# P1SwitchDemo.net
KiCad netlist of a schematic drawn in EAGLE
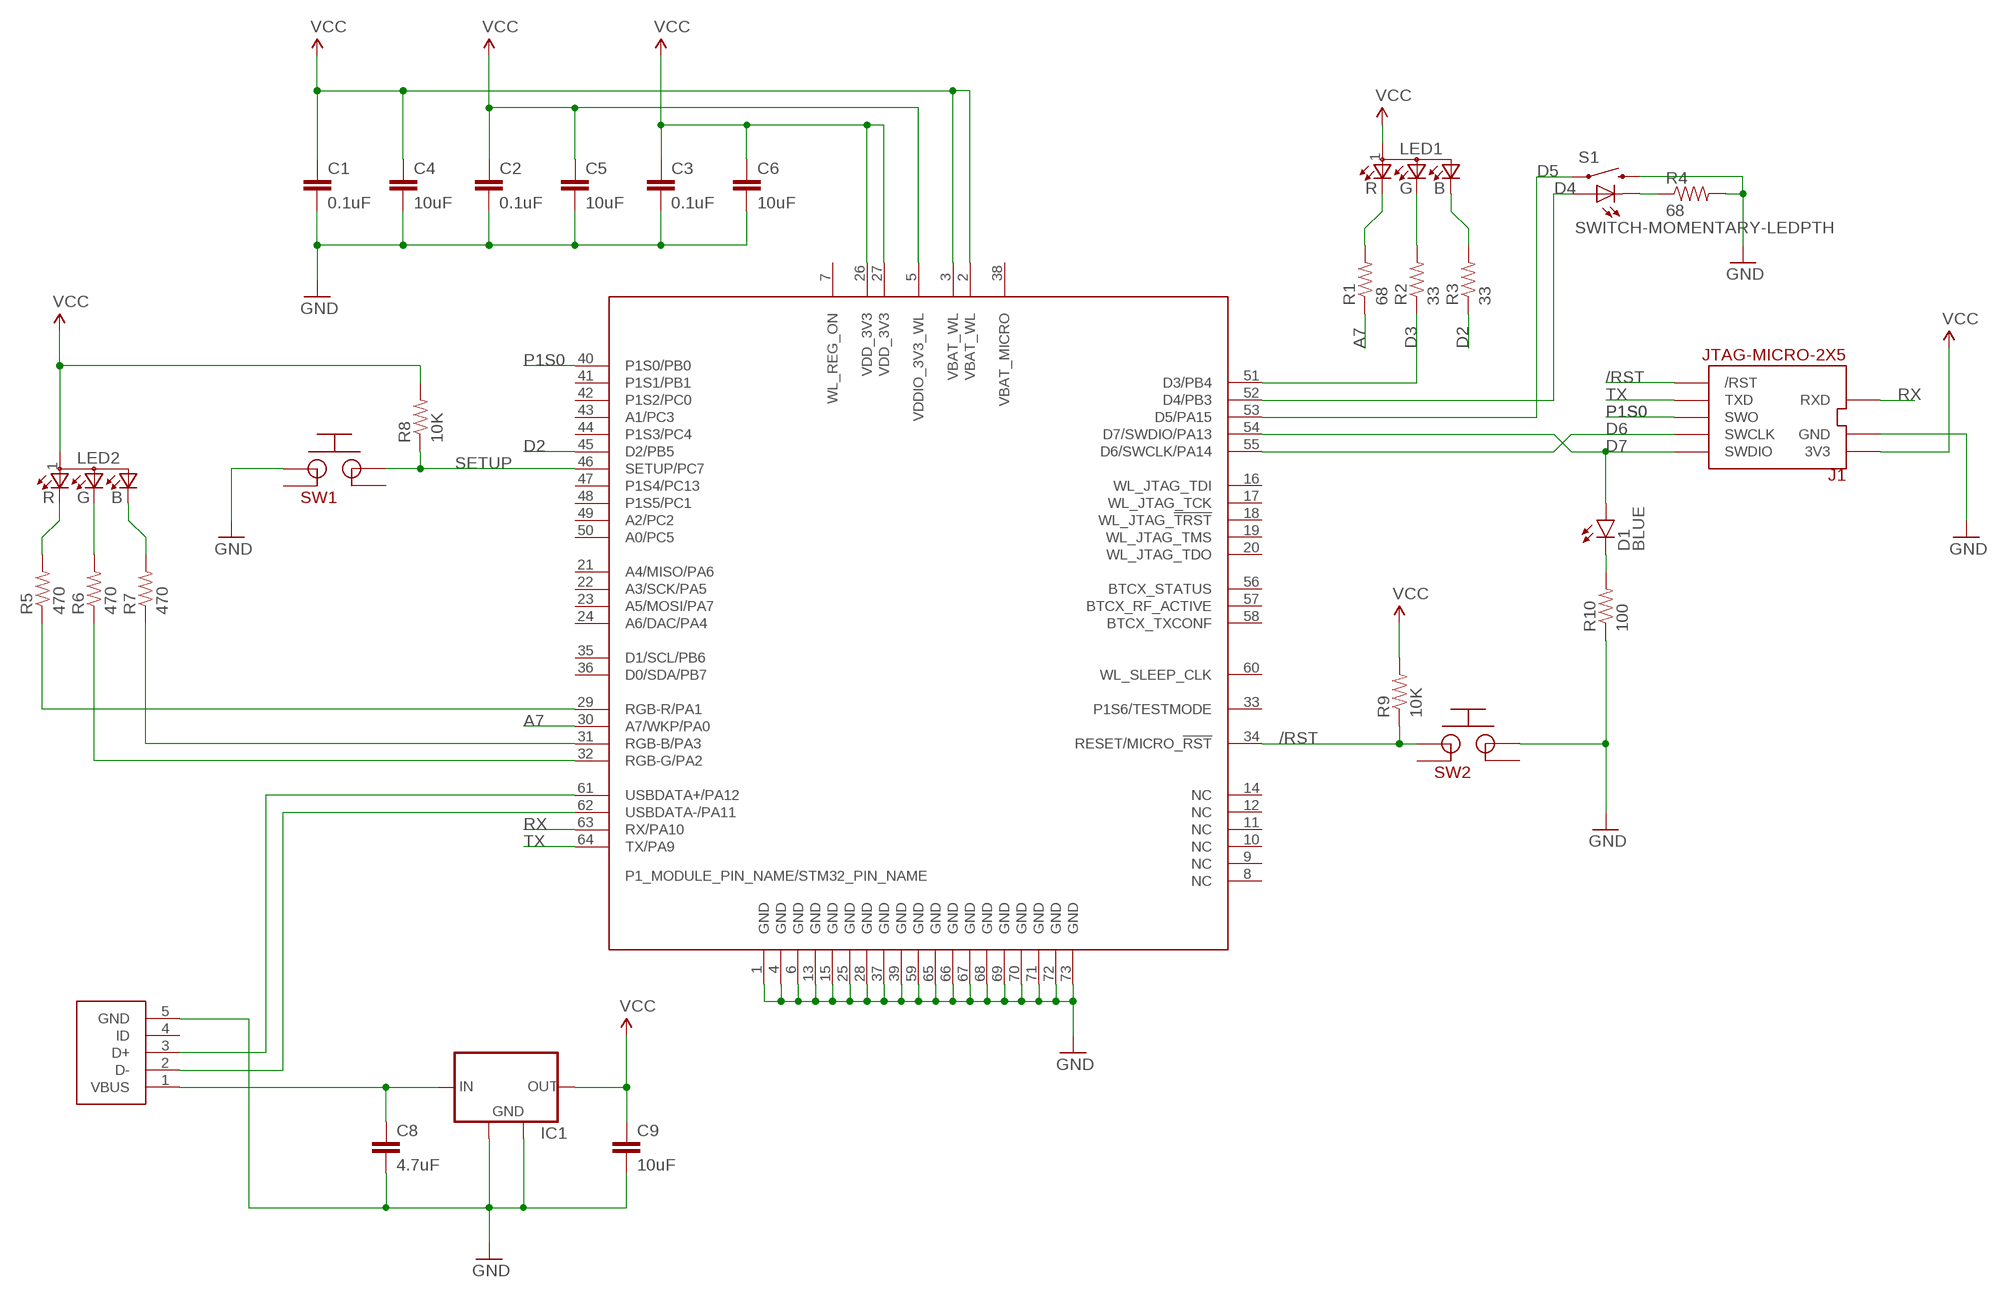
[diagram p0: schematic, sheet 1]

(export (version "E")
  (design (tool "Eeschema 10.0.6"))
  (components
    (comp (ref "C1")
      (value "0.1uF")
      (footprint "eagle-import:0603-CAP")
      (libsource (lib "eagle-import") (part "CAP-0.1UF-0603"))
    )
    (comp (ref "C2")
      (value "0.1uF")
      (footprint "eagle-import:0603-CAP")
      (libsource (lib "eagle-import") (part "CAP-0.1UF-0603"))
    )
    (comp (ref "C3")
      (value "0.1uF")
      (footprint "eagle-import:0603-CAP")
      (libsource (lib "eagle-import") (part "CAP-0.1UF-0603"))
    )
    (comp (ref "C4")
      (value "10uF")
      (footprint "eagle-import:0603-CAP")
      (libsource (lib "eagle-import") (part "CAP-10UF-0603"))
    )
    (comp (ref "C5")
      (value "10uF")
      (footprint "eagle-import:0603-CAP")
      (libsource (lib "eagle-import") (part "CAP-10UF-0603"))
    )
    (comp (ref "C6")
      (value "10uF")
      (footprint "eagle-import:0603-CAP")
      (libsource (lib "eagle-import") (part "CAP-10UF-0603"))
    )
    (comp (ref "C8")
      (value "4.7uF")
      (footprint "eagle-import:0603-CAP")
      (libsource (lib "eagle-import") (part "CAP-4.7UF-0603"))
    )
    (comp (ref "C9")
      (value "10uF")
      (footprint "eagle-import:0603-CAP")
      (libsource (lib "eagle-import") (part "CAP-10UF-0603"))
    )
    (comp (ref "D1")
      (value "BLUE")
      (footprint "eagle-import:LED-0603")
      (libsource (lib "eagle-import") (part "LED-BLUE0603"))
    )
    (comp (ref "IC1")
      (value "MCP1825S-SOT223")
      (footprint "eagle-import:SOT223")
      (libsource (lib "eagle-import") (part "MCP1825S-SOT223"))
    )
    (comp (ref "J1")
      (value "JTAG-MICRO-2X5")
      (footprint "eagle-import:JTAG-MICRO-2X5")
      (libsource (lib "eagle-import") (part "JTAG-MICRO-2X5"))
    )
    (comp (ref "LED1")
      (value "LED-RGB-CREE-SMD")
      (footprint "eagle-import:LED-RGB-CREE-SMD")
      (libsource (lib "eagle-import") (part "LED-RGB-CREE-SMD"))
    )
    (comp (ref "LED2")
      (value "LED-RGB-CREE-SMD")
      (footprint "eagle-import:LED-RGB-CREE-SMD")
      (libsource (lib "eagle-import") (part "LED-RGB-CREE-SMD"))
    )
    (comp (ref "R1")
      (value "68")
      (footprint "eagle-import:0603-RES")
      (libsource (lib "eagle-import") (part "RES-68-0603.DEV"))
    )
    (comp (ref "R2")
      (value "33")
      (footprint "eagle-import:0603-RES")
      (libsource (lib "eagle-import") (part "RES-33-0603.DEV"))
    )
    (comp (ref "R3")
      (value "33")
      (footprint "eagle-import:0603-RES")
      (libsource (lib "eagle-import") (part "RES-33-0603.DEV"))
    )
    (comp (ref "R4")
      (value "68")
      (footprint "eagle-import:0603-RES")
      (libsource (lib "eagle-import") (part "RES-68-0603.DEV"))
    )
    (comp (ref "R5")
      (value "470")
      (footprint "eagle-import:0603-RES")
      (libsource (lib "eagle-import") (part "RES-470-0603"))
    )
    (comp (ref "R6")
      (value "470")
      (footprint "eagle-import:0603-RES")
      (libsource (lib "eagle-import") (part "RES-470-0603"))
    )
    (comp (ref "R7")
      (value "470")
      (footprint "eagle-import:0603-RES")
      (libsource (lib "eagle-import") (part "RES-470-0603"))
    )
    (comp (ref "R8")
      (value "10K")
      (footprint "eagle-import:0603-RES")
      (libsource (lib "eagle-import") (part "RES-10K-06030603"))
    )
    (comp (ref "R9")
      (value "10K")
      (footprint "eagle-import:0603-RES")
      (libsource (lib "eagle-import") (part "RES-10K-06030603"))
    )
    (comp (ref "R10")
      (value "100")
      (footprint "eagle-import:0603-RES")
      (libsource (lib "eagle-import") (part "RES-100-0603.DEV"))
    )
    (comp (ref "S1")
      (value "SWITCH-MOMENTARY-LEDPTH")
      (footprint "eagle-import:TACTILE-PTH-LED-12MM")
      (libsource (lib "eagle-import") (part "SWITCH-MOMENTARY-LEDPTH"))
    )
    (comp (ref "SW1")
      (value "SWITCH-PTS645")
      (footprint "eagle-import:SWITCH-PTS645")
      (libsource (lib "eagle-import") (part "SWITCH-PTS645"))
    )
    (comp (ref "SW2")
      (value "SWITCH-PTS645")
      (footprint "eagle-import:SWITCH-PTS645")
      (libsource (lib "eagle-import") (part "SWITCH-PTS645"))
    )
    (comp (ref "U$4")
      (value "USB-MICRO-B-SOCKET-AMPHENOL")
      (footprint "eagle-import:USB-B-SMT-AMPHENOL")
      (libsource (lib "eagle-import") (part "USB-MICRO-B-SOCKET-AMPHENOL"))
    )
    (comp (ref "U$6")
      (value "P1")
      (footprint "eagle-import:WM-N-BM-14")
      (libsource (lib "eagle-import") (part "P1"))
    )
  )
  (nets
    (net (code "1") (name "/A7") (class "Default")
      (node (ref "R1") (pin "1") (pinfunction "1_1") (pintype "passive"))
      (node (ref "U$6") (pin "30") (pinfunction "A7/WKP/PA0_30") (pintype "bidirectional"))
    )
    (net (code "2") (name "/D2") (class "Default")
      (node (ref "R3") (pin "1") (pinfunction "1_1") (pintype "passive"))
      (node (ref "U$6") (pin "45") (pinfunction "D2/PB5_45") (pintype "bidirectional"))
    )
    (net (code "3") (name "/D3") (class "Default")
      (node (ref "R2") (pin "1") (pinfunction "1_1") (pintype "passive"))
      (node (ref "U$6") (pin "51") (pinfunction "D3/PB4_51") (pintype "bidirectional"))
    )
    (net (code "4") (name "/D4") (class "Default")
      (node (ref "S1") (pin "A") (pinfunction "A_A") (pintype "passive"))
      (node (ref "U$6") (pin "52") (pinfunction "D4/PB3_52") (pintype "bidirectional"))
    )
    (net (code "5") (name "/D5") (class "Default")
      (node (ref "S1") (pin "4") (pinfunction "1_4") (pintype "passive"))
      (node (ref "U$6") (pin "53") (pinfunction "D5/PA15_53") (pintype "bidirectional"))
    )
    (net (code "6") (name "/D6") (class "Default")
      (node (ref "J1") (pin "4") (pinfunction "SWCLK_4") (pintype "passive"))
      (node (ref "U$6") (pin "55") (pinfunction "D6/SWCLK/PA14_55") (pintype "bidirectional"))
    )
    (net (code "7") (name "/D7") (class "Default")
      (node (ref "D1") (pin "A") (pinfunction "A_A") (pintype "passive"))
      (node (ref "J1") (pin "2") (pinfunction "SWDIO_2") (pintype "passive"))
      (node (ref "U$6") (pin "54") (pinfunction "D7/SWDIO/PA13_54") (pintype "bidirectional"))
    )
    (net (code "8") (name "/P1S0") (class "Default")
      (node (ref "J1") (pin "6") (pinfunction "SWO_6") (pintype "passive"))
      (node (ref "U$6") (pin "40") (pinfunction "P1S0/PB0_40") (pintype "bidirectional"))
    )
    (net (code "9") (name "/RX") (class "Default")
      (node (ref "J1") (pin "7") (pinfunction "RXD_7") (pintype "passive"))
      (node (ref "U$6") (pin "63") (pinfunction "RX/PA10_63") (pintype "bidirectional"))
    )
    (net (code "10") (name "/SETUP") (class "Default")
      (node (ref "R8") (pin "1") (pinfunction "1_1") (pintype "passive"))
      (node (ref "SW1") (pin "3") (pinfunction "3_3") (pintype "passive"))
      (node (ref "U$6") (pin "46") (pinfunction "SETUP/PC7_46") (pintype "bidirectional"))
    )
    (net (code "11") (name "/TX") (class "Default")
      (node (ref "J1") (pin "8") (pinfunction "TXD_8") (pintype "passive"))
      (node (ref "U$6") (pin "64") (pinfunction "TX/PA9_64") (pintype "bidirectional"))
    )
    (net (code "12") (name "/{slash}RST") (class "Default")
      (node (ref "J1") (pin "10") (pinfunction "/RST_10") (pintype "passive"))
      (node (ref "R9") (pin "1") (pinfunction "1_1") (pintype "passive"))
      (node (ref "SW2") (pin "1") (pinfunction "1_1") (pintype "passive"))
      (node (ref "U$6") (pin "34") (pinfunction "RESET/MICRO_~{RST}_34") (pintype "bidirectional"))
    )
    (net (code "13") (name "GND") (class "Default")
      (node (ref "C1") (pin "2") (pinfunction "2_2") (pintype "passive"))
      (node (ref "C2") (pin "2") (pinfunction "2_2") (pintype "passive"))
      (node (ref "C3") (pin "2") (pinfunction "2_2") (pintype "passive"))
      (node (ref "C4") (pin "2") (pinfunction "2_2") (pintype "passive"))
      (node (ref "C5") (pin "2") (pinfunction "2_2") (pintype "passive"))
      (node (ref "C6") (pin "2") (pinfunction "2_2") (pintype "passive"))
      (node (ref "C8") (pin "2") (pinfunction "2_2") (pintype "passive"))
      (node (ref "C9") (pin "2") (pinfunction "2_2") (pintype "passive"))
      (node (ref "IC1") (pin "2") (pinfunction "GND_2") (pintype "power_in"))
      (node (ref "IC1") (pin "4") (pinfunction "GND_4") (pintype "power_in"))
      (node (ref "J1") (pin "3") (pinfunction "GND_3") (pintype "passive"))
      (node (ref "J1") (pin "5") (pinfunction "GND_5") (pintype "passive"))
      (node (ref "J1") (pin "9") (pinfunction "GND_9") (pintype "passive"))
      (node (ref "R10") (pin "1") (pinfunction "1_1") (pintype "passive"))
      (node (ref "R4") (pin "2") (pinfunction "2_2") (pintype "passive"))
      (node (ref "S1") (pin "2") (pinfunction "2_2") (pintype "passive"))
      (node (ref "SW1") (pin "1") (pinfunction "1_1") (pintype "passive"))
      (node (ref "SW2") (pin "3") (pinfunction "3_3") (pintype "passive"))
      (node (ref "U$4") (pin "5") (pinfunction "GND_5") (pintype "passive"))
      (node (ref "U$6") (pin "1") (pinfunction "GND_1") (pintype "bidirectional"))
      (node (ref "U$6") (pin "13") (pinfunction "GND_13") (pintype "bidirectional"))
      (node (ref "U$6") (pin "15") (pinfunction "GND_15") (pintype "bidirectional"))
      (node (ref "U$6") (pin "25") (pinfunction "GND_25") (pintype "bidirectional"))
      (node (ref "U$6") (pin "28") (pinfunction "GND_28") (pintype "bidirectional"))
      (node (ref "U$6") (pin "37") (pinfunction "GND_37") (pintype "bidirectional"))
      (node (ref "U$6") (pin "39") (pinfunction "GND_39") (pintype "bidirectional"))
      (node (ref "U$6") (pin "4") (pinfunction "GND_4") (pintype "bidirectional"))
      (node (ref "U$6") (pin "59") (pinfunction "GND_59") (pintype "bidirectional"))
      (node (ref "U$6") (pin "6") (pinfunction "GND_6") (pintype "bidirectional"))
      (node (ref "U$6") (pin "65") (pinfunction "GND_65") (pintype "bidirectional"))
      (node (ref "U$6") (pin "66") (pinfunction "GND_66") (pintype "bidirectional"))
      (node (ref "U$6") (pin "67") (pinfunction "GND_67") (pintype "bidirectional"))
      (node (ref "U$6") (pin "68") (pinfunction "GND_68") (pintype "bidirectional"))
      (node (ref "U$6") (pin "69") (pinfunction "GND_69") (pintype "bidirectional"))
      (node (ref "U$6") (pin "70") (pinfunction "GND_70") (pintype "bidirectional"))
      (node (ref "U$6") (pin "71") (pinfunction "GND_71") (pintype "bidirectional"))
      (node (ref "U$6") (pin "72") (pinfunction "GND_72") (pintype "bidirectional"))
      (node (ref "U$6") (pin "73") (pinfunction "GND_73") (pintype "bidirectional"))
    )
    (net (code "14") (name "Net-(D1-PadC)") (class "Default")
      (node (ref "D1") (pin "C") (pinfunction "C_C") (pintype "passive"))
      (node (ref "R10") (pin "2") (pinfunction "2_2") (pintype "passive"))
    )
    (net (code "15") (name "Net-(IC1-IN)") (class "Default")
      (node (ref "C8") (pin "1") (pinfunction "1_1") (pintype "passive"))
      (node (ref "IC1") (pin "1") (pinfunction "IN_1") (pintype "power_in"))
      (node (ref "U$4") (pin "1") (pinfunction "VBUS_1") (pintype "passive"))
    )
    (net (code "16") (name "Net-(LED1-B)") (class "Default")
      (node (ref "LED1") (pin "2") (pinfunction "B_2") (pintype "passive"))
      (node (ref "R3") (pin "2") (pinfunction "2_2") (pintype "passive"))
    )
    (net (code "17") (name "Net-(LED1-G)") (class "Default")
      (node (ref "LED1") (pin "3") (pinfunction "G_3") (pintype "passive"))
      (node (ref "R2") (pin "2") (pinfunction "2_2") (pintype "passive"))
    )
    (net (code "18") (name "Net-(LED1-R)") (class "Default")
      (node (ref "LED1") (pin "4") (pinfunction "R_4") (pintype "passive"))
      (node (ref "R1") (pin "2") (pinfunction "2_2") (pintype "passive"))
    )
    (net (code "19") (name "Net-(LED2-B)") (class "Default")
      (node (ref "LED2") (pin "2") (pinfunction "B_2") (pintype "passive"))
      (node (ref "R7") (pin "2") (pinfunction "2_2") (pintype "passive"))
    )
    (net (code "20") (name "Net-(LED2-G)") (class "Default")
      (node (ref "LED2") (pin "3") (pinfunction "G_3") (pintype "passive"))
      (node (ref "R6") (pin "2") (pinfunction "2_2") (pintype "passive"))
    )
    (net (code "21") (name "Net-(LED2-R)") (class "Default")
      (node (ref "LED2") (pin "4") (pinfunction "R_4") (pintype "passive"))
      (node (ref "R5") (pin "2") (pinfunction "2_2") (pintype "passive"))
    )
    (net (code "22") (name "Net-(R4-Pad1)") (class "Default")
      (node (ref "R4") (pin "1") (pinfunction "1_1") (pintype "passive"))
      (node (ref "S1") (pin "C") (pinfunction "C_C") (pintype "passive"))
    )
    (net (code "23") (name "Net-(U$4-D+)") (class "Default")
      (node (ref "U$4") (pin "3") (pinfunction "D+_3") (pintype "passive"))
      (node (ref "U$6") (pin "61") (pinfunction "USBDATA+/PA12_61") (pintype "bidirectional"))
    )
    (net (code "24") (name "Net-(U$4-D-)") (class "Default")
      (node (ref "U$4") (pin "2") (pinfunction "D-_2") (pintype "passive"))
      (node (ref "U$6") (pin "62") (pinfunction "USBDATA-/PA11_62") (pintype "bidirectional"))
    )
    (net (code "25") (name "Net-(U$6-RGB-B{slash}PA3)") (class "Default")
      (node (ref "R7") (pin "1") (pinfunction "1_1") (pintype "passive"))
      (node (ref "U$6") (pin "31") (pinfunction "RGB-B/PA3_31") (pintype "bidirectional"))
    )
    (net (code "26") (name "Net-(U$6-RGB-G{slash}PA2)") (class "Default")
      (node (ref "R6") (pin "1") (pinfunction "1_1") (pintype "passive"))
      (node (ref "U$6") (pin "32") (pinfunction "RGB-G/PA2_32") (pintype "bidirectional"))
    )
    (net (code "27") (name "Net-(U$6-RGB-R{slash}PA1)") (class "Default")
      (node (ref "R5") (pin "1") (pinfunction "1_1") (pintype "passive"))
      (node (ref "U$6") (pin "29") (pinfunction "RGB-R/PA1_29") (pintype "bidirectional"))
    )
    (net (code "28") (name "VCC") (class "Default")
      (node (ref "C1") (pin "1") (pinfunction "1_1") (pintype "passive"))
      (node (ref "C2") (pin "1") (pinfunction "1_1") (pintype "passive"))
      (node (ref "C3") (pin "1") (pinfunction "1_1") (pintype "passive"))
      (node (ref "C4") (pin "1") (pinfunction "1_1") (pintype "passive"))
      (node (ref "C5") (pin "1") (pinfunction "1_1") (pintype "passive"))
      (node (ref "C6") (pin "1") (pinfunction "1_1") (pintype "passive"))
      (node (ref "C9") (pin "1") (pinfunction "1_1") (pintype "passive"))
      (node (ref "IC1") (pin "3") (pinfunction "OUT_3") (pintype "passive"))
      (node (ref "J1") (pin "1") (pinfunction "3V3_1") (pintype "passive"))
      (node (ref "LED1") (pin "1") (pinfunction "A_1") (pintype "passive"))
      (node (ref "LED2") (pin "1") (pinfunction "A_1") (pintype "passive"))
      (node (ref "R8") (pin "2") (pinfunction "2_2") (pintype "passive"))
      (node (ref "R9") (pin "2") (pinfunction "2_2") (pintype "passive"))
      (node (ref "U$6") (pin "2") (pinfunction "VBAT_WL_2") (pintype "bidirectional"))
      (node (ref "U$6") (pin "26") (pinfunction "VDD_3V3_26") (pintype "bidirectional"))
      (node (ref "U$6") (pin "27") (pinfunction "VDD_3V3_27") (pintype "bidirectional"))
      (node (ref "U$6") (pin "3") (pinfunction "VBAT_WL_3") (pintype "bidirectional"))
      (node (ref "U$6") (pin "5") (pinfunction "VDDIO_3V3_WL_5") (pintype "bidirectional"))
    )
    (net (code "29") (name "unconnected-(SW1-Pad2)") (class "Default")
      (node (ref "SW1") (pin "2") (pinfunction "2_2") (pintype "passive"))
    )
    (net (code "30") (name "unconnected-(SW1-Pad4)") (class "Default")
      (node (ref "SW1") (pin "4") (pinfunction "4_4") (pintype "passive"))
    )
    (net (code "31") (name "unconnected-(SW2-Pad2)") (class "Default")
      (node (ref "SW2") (pin "2") (pinfunction "2_2") (pintype "passive"))
    )
    (net (code "32") (name "unconnected-(SW2-Pad4)") (class "Default")
      (node (ref "SW2") (pin "4") (pinfunction "4_4") (pintype "passive"))
    )
    (net (code "33") (name "unconnected-(U$4-ID-Pad4)") (class "Default")
      (node (ref "U$4") (pin "4") (pinfunction "ID_4") (pintype "passive"))
    )
    (net (code "34") (name "unconnected-(U$6-A0{slash}PC5-Pad50)") (class "Default")
      (node (ref "U$6") (pin "50") (pinfunction "A0/PC5_50") (pintype "bidirectional"))
    )
    (net (code "35") (name "unconnected-(U$6-A1{slash}PC3-Pad43)") (class "Default")
      (node (ref "U$6") (pin "43") (pinfunction "A1/PC3_43") (pintype "bidirectional"))
    )
    (net (code "36") (name "unconnected-(U$6-A2{slash}PC2-Pad49)") (class "Default")
      (node (ref "U$6") (pin "49") (pinfunction "A2/PC2_49") (pintype "bidirectional"))
    )
    (net (code "37") (name "unconnected-(U$6-A3{slash}SCK{slash}PA5-Pad22)") (class "Default")
      (node (ref "U$6") (pin "22") (pinfunction "A3/SCK/PA5_22") (pintype "bidirectional"))
    )
    (net (code "38") (name "unconnected-(U$6-A4{slash}MISO{slash}PA6-Pad21)") (class "Default")
      (node (ref "U$6") (pin "21") (pinfunction "A4/MISO/PA6_21") (pintype "bidirectional"))
    )
    (net (code "39") (name "unconnected-(U$6-A5{slash}MOSI{slash}PA7-Pad23)") (class "Default")
      (node (ref "U$6") (pin "23") (pinfunction "A5/MOSI/PA7_23") (pintype "bidirectional"))
    )
    (net (code "40") (name "unconnected-(U$6-A6{slash}DAC{slash}PA4-Pad24)") (class "Default")
      (node (ref "U$6") (pin "24") (pinfunction "A6/DAC/PA4_24") (pintype "bidirectional"))
    )
    (net (code "41") (name "unconnected-(U$6-BTCX_RF_ACTIVE-Pad57)") (class "Default")
      (node (ref "U$6") (pin "57") (pinfunction "BTCX_RF_ACTIVE_57") (pintype "bidirectional"))
    )
    (net (code "42") (name "unconnected-(U$6-BTCX_STATUS-Pad56)") (class "Default")
      (node (ref "U$6") (pin "56") (pinfunction "BTCX_STATUS_56") (pintype "bidirectional"))
    )
    (net (code "43") (name "unconnected-(U$6-BTCX_TXCONF-Pad58)") (class "Default")
      (node (ref "U$6") (pin "58") (pinfunction "BTCX_TXCONF_58") (pintype "bidirectional"))
    )
    (net (code "44") (name "unconnected-(U$6-D0{slash}SDA{slash}PB7-Pad36)") (class "Default")
      (node (ref "U$6") (pin "36") (pinfunction "D0/SDA/PB7_36") (pintype "bidirectional"))
    )
    (net (code "45") (name "unconnected-(U$6-D1{slash}SCL{slash}PB6-Pad35)") (class "Default")
      (node (ref "U$6") (pin "35") (pinfunction "D1/SCL/PB6_35") (pintype "bidirectional"))
    )
    (net (code "46") (name "unconnected-(U$6-NC-Pad8)") (class "Default")
      (node (ref "U$6") (pin "8") (pinfunction "NC_8") (pintype "bidirectional"))
    )
    (net (code "47") (name "unconnected-(U$6-NC-Pad9)") (class "Default")
      (node (ref "U$6") (pin "9") (pinfunction "NC_9") (pintype "bidirectional"))
    )
    (net (code "48") (name "unconnected-(U$6-NC-Pad10)") (class "Default")
      (node (ref "U$6") (pin "10") (pinfunction "NC_10") (pintype "bidirectional"))
    )
    (net (code "49") (name "unconnected-(U$6-NC-Pad11)") (class "Default")
      (node (ref "U$6") (pin "11") (pinfunction "NC_11") (pintype "bidirectional"))
    )
    (net (code "50") (name "unconnected-(U$6-NC-Pad12)") (class "Default")
      (node (ref "U$6") (pin "12") (pinfunction "NC_12") (pintype "bidirectional"))
    )
    (net (code "51") (name "unconnected-(U$6-NC-Pad14)") (class "Default")
      (node (ref "U$6") (pin "14") (pinfunction "NC_14") (pintype "bidirectional"))
    )
    (net (code "52") (name "unconnected-(U$6-P1S1{slash}PB1-Pad41)") (class "Default")
      (node (ref "U$6") (pin "41") (pinfunction "P1S1/PB1_41") (pintype "bidirectional"))
    )
    (net (code "53") (name "unconnected-(U$6-P1S2{slash}PC0-Pad42)") (class "Default")
      (node (ref "U$6") (pin "42") (pinfunction "P1S2/PC0_42") (pintype "bidirectional"))
    )
    (net (code "54") (name "unconnected-(U$6-P1S3{slash}PC4-Pad44)") (class "Default")
      (node (ref "U$6") (pin "44") (pinfunction "P1S3/PC4_44") (pintype "bidirectional"))
    )
    (net (code "55") (name "unconnected-(U$6-P1S4{slash}PC13-Pad47)") (class "Default")
      (node (ref "U$6") (pin "47") (pinfunction "P1S4/PC13_47") (pintype "bidirectional"))
    )
    (net (code "56") (name "unconnected-(U$6-P1S5{slash}PC1-Pad48)") (class "Default")
      (node (ref "U$6") (pin "48") (pinfunction "P1S5/PC1_48") (pintype "bidirectional"))
    )
    (net (code "57") (name "unconnected-(U$6-P1S6{slash}TESTMODE-Pad33)") (class "Default")
      (node (ref "U$6") (pin "33") (pinfunction "P1S6/TESTMODE_33") (pintype "bidirectional"))
    )
    (net (code "58") (name "unconnected-(U$6-VBAT_MICRO-Pad38)") (class "Default")
      (node (ref "U$6") (pin "38") (pinfunction "VBAT_MICRO_38") (pintype "bidirectional"))
    )
    (net (code "59") (name "unconnected-(U$6-WL_JTAG_TCK-Pad17)") (class "Default")
      (node (ref "U$6") (pin "17") (pinfunction "WL_JTAG_TCK_17") (pintype "bidirectional"))
    )
    (net (code "60") (name "unconnected-(U$6-WL_JTAG_TDI-Pad16)") (class "Default")
      (node (ref "U$6") (pin "16") (pinfunction "WL_JTAG_TDI_16") (pintype "bidirectional"))
    )
    (net (code "61") (name "unconnected-(U$6-WL_JTAG_TDO-Pad20)") (class "Default")
      (node (ref "U$6") (pin "20") (pinfunction "WL_JTAG_TDO_20") (pintype "bidirectional"))
    )
    (net (code "62") (name "unconnected-(U$6-WL_JTAG_TMS-Pad19)") (class "Default")
      (node (ref "U$6") (pin "19") (pinfunction "WL_JTAG_TMS_19") (pintype "bidirectional"))
    )
    (net (code "63") (name "unconnected-(U$6-WL_JTAG_~{TRST}-Pad18)") (class "Default")
      (node (ref "U$6") (pin "18") (pinfunction "WL_JTAG_~{TRST}_18") (pintype "bidirectional"))
    )
    (net (code "64") (name "unconnected-(U$6-WL_REG_ON-Pad7)") (class "Default")
      (node (ref "U$6") (pin "7") (pinfunction "WL_REG_ON_7") (pintype "bidirectional"))
    )
    (net (code "65") (name "unconnected-(U$6-WL_SLEEP_CLK-Pad60)") (class "Default")
      (node (ref "U$6") (pin "60") (pinfunction "WL_SLEEP_CLK_60") (pintype "bidirectional"))
    )
  )
)
